# TestBed.net
KiCad netlist of a schematic drawn in EAGLE
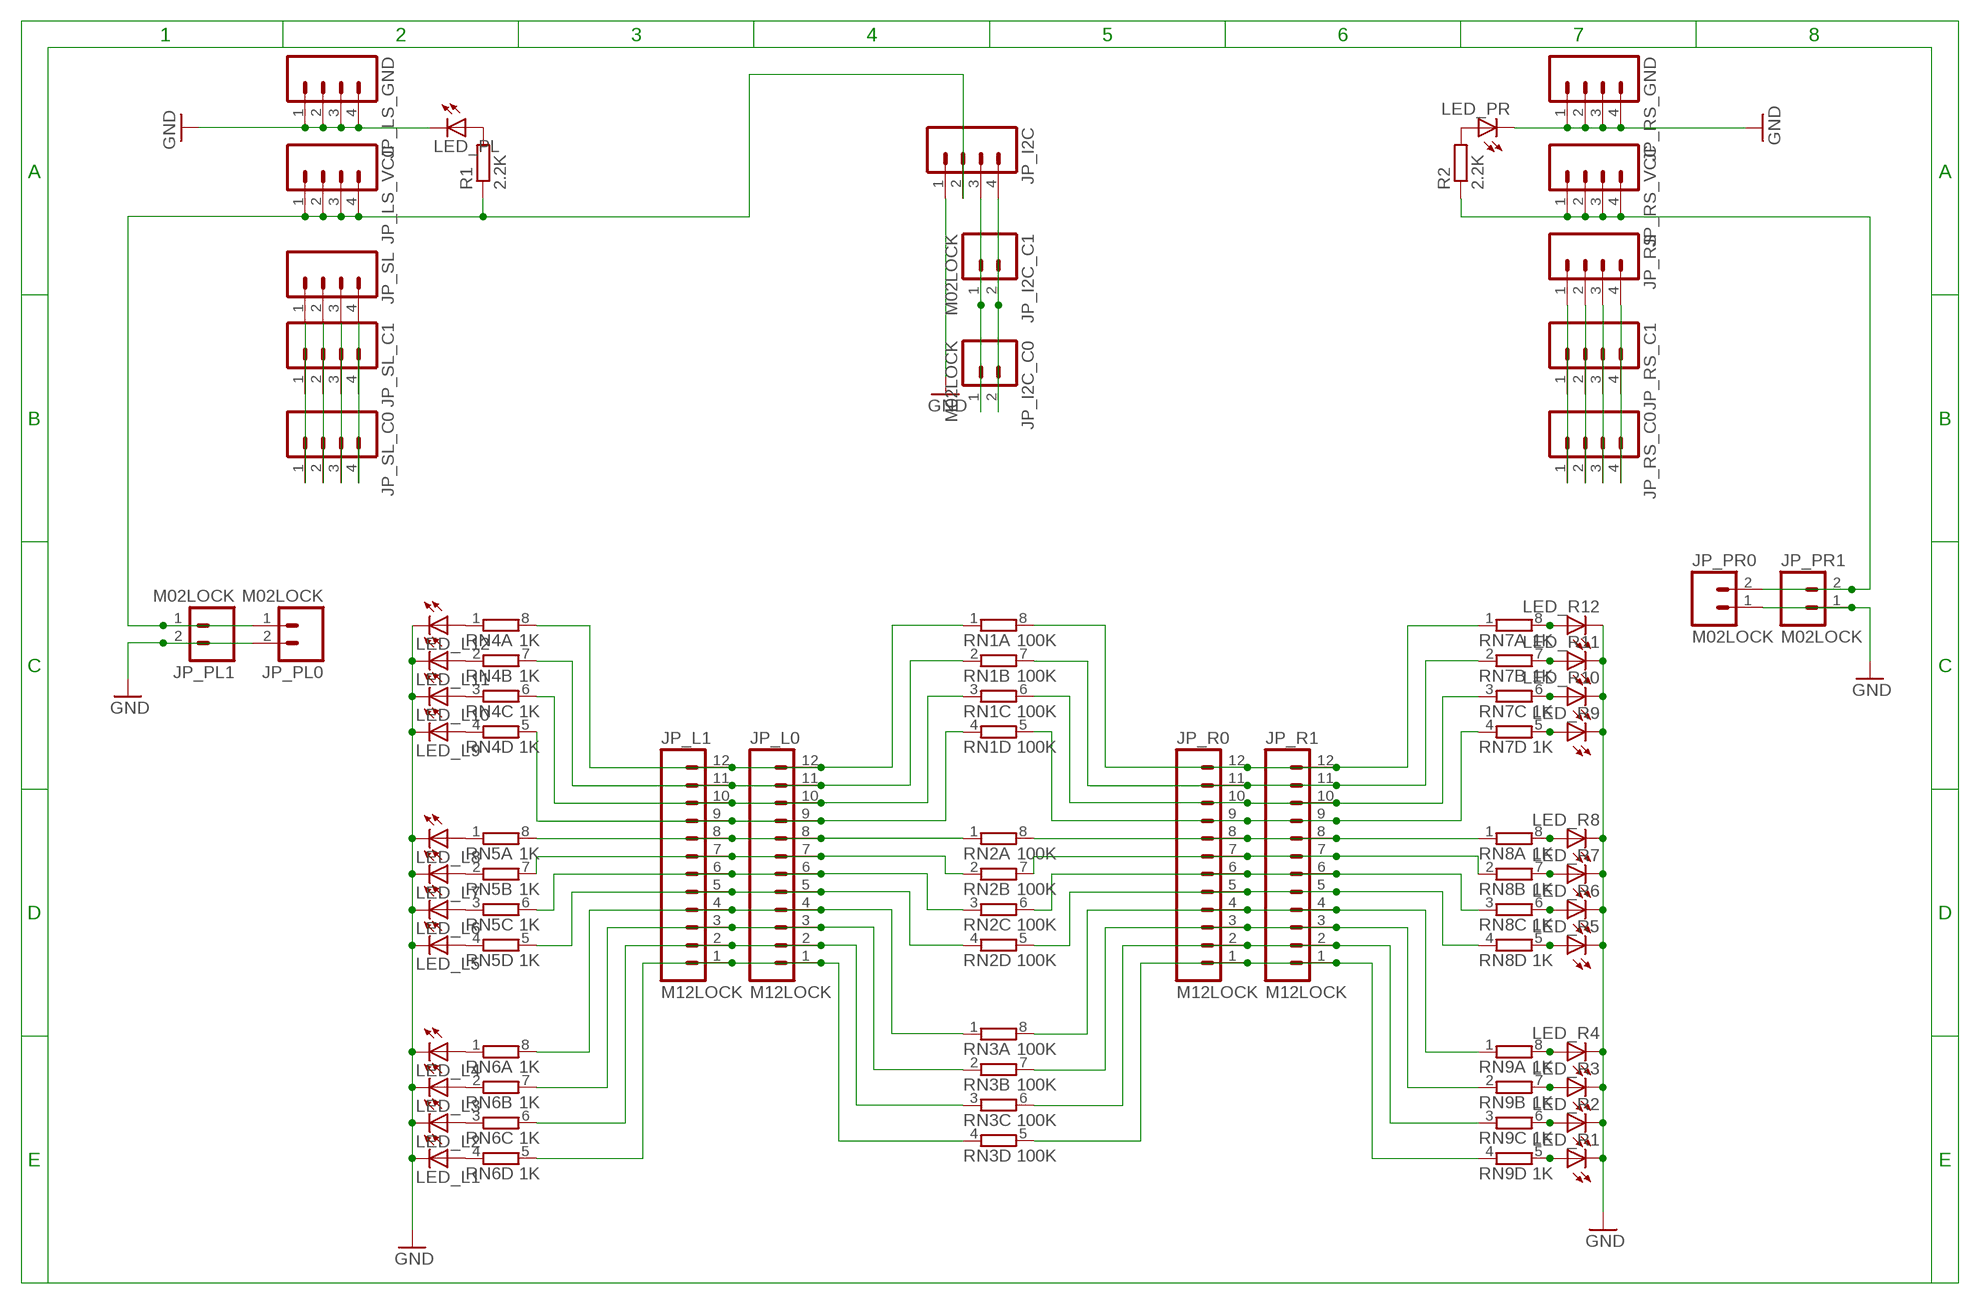
[diagram p0: schematic, sheet 1]

(export (version "E")
  (design (tool "Eeschema 10.0.6"))
  (components
    (comp (ref "JP_I2C")
      (value "M04LOCK")
      (footprint "eagle-import:1X04_LOCK")
      (libsource (lib "eagle-import") (part "M04LOCK"))
    )
    (comp (ref "JP_I2C_C0")
      (value "M02LOCK")
      (footprint "eagle-import:1X02_LOCK")
      (libsource (lib "eagle-import") (part "M02LOCK"))
    )
    (comp (ref "JP_I2C_C1")
      (value "M02LOCK")
      (footprint "eagle-import:1X02_LOCK")
      (libsource (lib "eagle-import") (part "M02LOCK"))
    )
    (comp (ref "JP_L0")
      (value "M12LOCK")
      (footprint "eagle-import:1X12_LOCK")
      (libsource (lib "eagle-import") (part "M12LOCK"))
    )
    (comp (ref "JP_L1")
      (value "M12LOCK")
      (footprint "eagle-import:1X12_LOCK")
      (libsource (lib "eagle-import") (part "M12LOCK"))
    )
    (comp (ref "JP_LS_GND")
      (value "M04LOCK")
      (footprint "eagle-import:1X04_LOCK")
      (libsource (lib "eagle-import") (part "M04LOCK"))
    )
    (comp (ref "JP_LS_VCC")
      (value "M04LOCK")
      (footprint "eagle-import:1X04_LOCK")
      (libsource (lib "eagle-import") (part "M04LOCK"))
    )
    (comp (ref "JP_PL0")
      (value "M02LOCK")
      (footprint "eagle-import:1X02_LOCK")
      (libsource (lib "eagle-import") (part "M02LOCK"))
    )
    (comp (ref "JP_PL1")
      (value "M02LOCK")
      (footprint "eagle-import:1X02_LOCK")
      (libsource (lib "eagle-import") (part "M02LOCK"))
    )
    (comp (ref "JP_PR0")
      (value "M02LOCK")
      (footprint "eagle-import:1X02_LOCK")
      (libsource (lib "eagle-import") (part "M02LOCK"))
    )
    (comp (ref "JP_PR1")
      (value "M02LOCK")
      (footprint "eagle-import:1X02_LOCK")
      (libsource (lib "eagle-import") (part "M02LOCK"))
    )
    (comp (ref "JP_R0")
      (value "M12LOCK")
      (footprint "eagle-import:1X12_LOCK")
      (libsource (lib "eagle-import") (part "M12LOCK"))
    )
    (comp (ref "JP_R1")
      (value "M12LOCK")
      (footprint "eagle-import:1X12_LOCK")
      (libsource (lib "eagle-import") (part "M12LOCK"))
    )
    (comp (ref "JP_RS")
      (value "M04LOCK")
      (footprint "eagle-import:1X04_LOCK")
      (libsource (lib "eagle-import") (part "M04LOCK"))
    )
    (comp (ref "JP_RS_C0")
      (value "M04LOCK")
      (footprint "eagle-import:1X04_LOCK")
      (libsource (lib "eagle-import") (part "M04LOCK"))
    )
    (comp (ref "JP_RS_C1")
      (value "M04LOCK")
      (footprint "eagle-import:1X04_LOCK")
      (libsource (lib "eagle-import") (part "M04LOCK"))
    )
    (comp (ref "JP_RS_GND")
      (value "M04LOCK")
      (footprint "eagle-import:1X04_LOCK")
      (libsource (lib "eagle-import") (part "M04LOCK"))
    )
    (comp (ref "JP_RS_VCC")
      (value "M04LOCK")
      (footprint "eagle-import:1X04_LOCK")
      (libsource (lib "eagle-import") (part "M04LOCK"))
    )
    (comp (ref "JP_SL")
      (value "M04LOCK")
      (footprint "eagle-import:1X04_LOCK")
      (libsource (lib "eagle-import") (part "M04LOCK"))
    )
    (comp (ref "JP_SL_C0")
      (value "M04LOCK")
      (footprint "eagle-import:1X04_LOCK")
      (libsource (lib "eagle-import") (part "M04LOCK"))
    )
    (comp (ref "JP_SL_C1")
      (value "M04LOCK")
      (footprint "eagle-import:1X04_LOCK")
      (libsource (lib "eagle-import") (part "M04LOCK"))
    )
    (comp (ref "LED_L1")
      (value "LEDCHIP-LED0805")
      (footprint "eagle-import:CHIP-LED0805")
      (libsource (lib "eagle-import") (part "LEDCHIP-LED0805"))
    )
    (comp (ref "LED_L2")
      (value "LEDCHIP-LED0805")
      (footprint "eagle-import:CHIP-LED0805")
      (libsource (lib "eagle-import") (part "LEDCHIP-LED0805"))
    )
    (comp (ref "LED_L3")
      (value "LEDCHIP-LED0805")
      (footprint "eagle-import:CHIP-LED0805")
      (libsource (lib "eagle-import") (part "LEDCHIP-LED0805"))
    )
    (comp (ref "LED_L4")
      (value "LEDCHIP-LED0805")
      (footprint "eagle-import:CHIP-LED0805")
      (libsource (lib "eagle-import") (part "LEDCHIP-LED0805"))
    )
    (comp (ref "LED_L5")
      (value "LEDCHIP-LED0805")
      (footprint "eagle-import:CHIP-LED0805")
      (libsource (lib "eagle-import") (part "LEDCHIP-LED0805"))
    )
    (comp (ref "LED_L6")
      (value "LEDCHIP-LED0805")
      (footprint "eagle-import:CHIP-LED0805")
      (libsource (lib "eagle-import") (part "LEDCHIP-LED0805"))
    )
    (comp (ref "LED_L7")
      (value "LEDCHIP-LED0805")
      (footprint "eagle-import:CHIP-LED0805")
      (libsource (lib "eagle-import") (part "LEDCHIP-LED0805"))
    )
    (comp (ref "LED_L8")
      (value "LEDCHIP-LED0805")
      (footprint "eagle-import:CHIP-LED0805")
      (libsource (lib "eagle-import") (part "LEDCHIP-LED0805"))
    )
    (comp (ref "LED_L9")
      (value "LEDCHIP-LED0805")
      (footprint "eagle-import:CHIP-LED0805")
      (libsource (lib "eagle-import") (part "LEDCHIP-LED0805"))
    )
    (comp (ref "LED_L10")
      (value "LEDCHIP-LED0805")
      (footprint "eagle-import:CHIP-LED0805")
      (libsource (lib "eagle-import") (part "LEDCHIP-LED0805"))
    )
    (comp (ref "LED_L11")
      (value "LEDCHIP-LED0805")
      (footprint "eagle-import:CHIP-LED0805")
      (libsource (lib "eagle-import") (part "LEDCHIP-LED0805"))
    )
    (comp (ref "LED_L12")
      (value "LEDCHIP-LED0805")
      (footprint "eagle-import:CHIP-LED0805")
      (libsource (lib "eagle-import") (part "LEDCHIP-LED0805"))
    )
    (comp (ref "LED_PL")
      (value "LEDCHIP-LED0805")
      (footprint "eagle-import:CHIP-LED0805")
      (libsource (lib "eagle-import") (part "LEDCHIP-LED0805"))
    )
    (comp (ref "LED_PR")
      (value "LEDCHIP-LED0805")
      (footprint "eagle-import:CHIP-LED0805")
      (libsource (lib "eagle-import") (part "LEDCHIP-LED0805"))
    )
    (comp (ref "LED_R1")
      (value "LEDCHIP-LED0805")
      (footprint "eagle-import:CHIP-LED0805")
      (libsource (lib "eagle-import") (part "LEDCHIP-LED0805"))
    )
    (comp (ref "LED_R2")
      (value "LEDCHIP-LED0805")
      (footprint "eagle-import:CHIP-LED0805")
      (libsource (lib "eagle-import") (part "LEDCHIP-LED0805"))
    )
    (comp (ref "LED_R3")
      (value "LEDCHIP-LED0805")
      (footprint "eagle-import:CHIP-LED0805")
      (libsource (lib "eagle-import") (part "LEDCHIP-LED0805"))
    )
    (comp (ref "LED_R4")
      (value "LEDCHIP-LED0805")
      (footprint "eagle-import:CHIP-LED0805")
      (libsource (lib "eagle-import") (part "LEDCHIP-LED0805"))
    )
    (comp (ref "LED_R5")
      (value "LEDCHIP-LED0805")
      (footprint "eagle-import:CHIP-LED0805")
      (libsource (lib "eagle-import") (part "LEDCHIP-LED0805"))
    )
    (comp (ref "LED_R6")
      (value "LEDCHIP-LED0805")
      (footprint "eagle-import:CHIP-LED0805")
      (libsource (lib "eagle-import") (part "LEDCHIP-LED0805"))
    )
    (comp (ref "LED_R7")
      (value "LEDCHIP-LED0805")
      (footprint "eagle-import:CHIP-LED0805")
      (libsource (lib "eagle-import") (part "LEDCHIP-LED0805"))
    )
    (comp (ref "LED_R8")
      (value "LEDCHIP-LED0805")
      (footprint "eagle-import:CHIP-LED0805")
      (libsource (lib "eagle-import") (part "LEDCHIP-LED0805"))
    )
    (comp (ref "LED_R9")
      (value "LEDCHIP-LED0805")
      (footprint "eagle-import:CHIP-LED0805")
      (libsource (lib "eagle-import") (part "LEDCHIP-LED0805"))
    )
    (comp (ref "LED_R10")
      (value "LEDCHIP-LED0805")
      (footprint "eagle-import:CHIP-LED0805")
      (libsource (lib "eagle-import") (part "LEDCHIP-LED0805"))
    )
    (comp (ref "LED_R11")
      (value "LEDCHIP-LED0805")
      (footprint "eagle-import:CHIP-LED0805")
      (libsource (lib "eagle-import") (part "LEDCHIP-LED0805"))
    )
    (comp (ref "LED_R12")
      (value "LEDCHIP-LED0805")
      (footprint "eagle-import:CHIP-LED0805")
      (libsource (lib "eagle-import") (part "LEDCHIP-LED0805"))
    )
    (comp (ref "R1")
      (value "2.2K")
      (footprint "eagle-import:M0805")
      (libsource (lib "eagle-import") (part "R-EU_M0805"))
    )
    (comp (ref "R2")
      (value "2.2K")
      (footprint "eagle-import:M0805")
      (libsource (lib "eagle-import") (part "R-EU_M0805"))
    )
    (comp (ref "RN1")
      (value "100K")
      (footprint "eagle-import:EXBS8V")
      (libsource (lib "eagle-import") (part "4R-NEXBS8V"))
    )
    (comp (ref "RN2")
      (value "100K")
      (footprint "eagle-import:EXBS8V")
      (libsource (lib "eagle-import") (part "4R-NEXBS8V"))
    )
    (comp (ref "RN3")
      (value "100K")
      (footprint "eagle-import:EXBS8V")
      (libsource (lib "eagle-import") (part "4R-NEXBS8V"))
    )
    (comp (ref "RN4")
      (value "1K")
      (footprint "eagle-import:EXBS8V")
      (libsource (lib "eagle-import") (part "4R-NEXBS8V"))
    )
    (comp (ref "RN5")
      (value "1K")
      (footprint "eagle-import:EXBS8V")
      (libsource (lib "eagle-import") (part "4R-NEXBS8V"))
    )
    (comp (ref "RN6")
      (value "1K")
      (footprint "eagle-import:EXBS8V")
      (libsource (lib "eagle-import") (part "4R-NEXBS8V"))
    )
    (comp (ref "RN7")
      (value "1K")
      (footprint "eagle-import:EXBS8V")
      (libsource (lib "eagle-import") (part "4R-NEXBS8V"))
    )
    (comp (ref "RN8")
      (value "1K")
      (footprint "eagle-import:EXBS8V")
      (libsource (lib "eagle-import") (part "4R-NEXBS8V"))
    )
    (comp (ref "RN9")
      (value "1K")
      (footprint "eagle-import:EXBS8V")
      (libsource (lib "eagle-import") (part "4R-NEXBS8V"))
    )
  )
  (nets
    (net (code "1") (name "GND") (class "Default")
      (node (ref "JP_I2C") (pin "1") (pinfunction "1_1") (pintype "passive"))
      (node (ref "JP_LS_GND") (pin "1") (pinfunction "1_1") (pintype "passive"))
      (node (ref "JP_LS_GND") (pin "2") (pinfunction "2_2") (pintype "passive"))
      (node (ref "JP_LS_GND") (pin "3") (pinfunction "3_3") (pintype "passive"))
      (node (ref "JP_LS_GND") (pin "4") (pinfunction "4_4") (pintype "passive"))
      (node (ref "JP_PL0") (pin "2") (pinfunction "2_2") (pintype "passive"))
      (node (ref "JP_PL1") (pin "2") (pinfunction "2_2") (pintype "passive"))
      (node (ref "JP_PR0") (pin "1") (pinfunction "1_1") (pintype "passive"))
      (node (ref "JP_PR1") (pin "1") (pinfunction "1_1") (pintype "passive"))
      (node (ref "JP_RS_GND") (pin "1") (pinfunction "1_1") (pintype "passive"))
      (node (ref "JP_RS_GND") (pin "2") (pinfunction "2_2") (pintype "passive"))
      (node (ref "JP_RS_GND") (pin "3") (pinfunction "3_3") (pintype "passive"))
      (node (ref "JP_RS_GND") (pin "4") (pinfunction "4_4") (pintype "passive"))
      (node (ref "LED_L1") (pin "C") (pinfunction "C_C") (pintype "passive"))
      (node (ref "LED_L10") (pin "C") (pinfunction "C_C") (pintype "passive"))
      (node (ref "LED_L11") (pin "C") (pinfunction "C_C") (pintype "passive"))
      (node (ref "LED_L12") (pin "C") (pinfunction "C_C") (pintype "passive"))
      (node (ref "LED_L2") (pin "C") (pinfunction "C_C") (pintype "passive"))
      (node (ref "LED_L3") (pin "C") (pinfunction "C_C") (pintype "passive"))
      (node (ref "LED_L4") (pin "C") (pinfunction "C_C") (pintype "passive"))
      (node (ref "LED_L5") (pin "C") (pinfunction "C_C") (pintype "passive"))
      (node (ref "LED_L6") (pin "C") (pinfunction "C_C") (pintype "passive"))
      (node (ref "LED_L7") (pin "C") (pinfunction "C_C") (pintype "passive"))
      (node (ref "LED_L8") (pin "C") (pinfunction "C_C") (pintype "passive"))
      (node (ref "LED_L9") (pin "C") (pinfunction "C_C") (pintype "passive"))
      (node (ref "LED_PL") (pin "C") (pinfunction "C_C") (pintype "passive"))
      (node (ref "LED_PR") (pin "C") (pinfunction "C_C") (pintype "passive"))
      (node (ref "LED_R1") (pin "C") (pinfunction "C_C") (pintype "passive"))
      (node (ref "LED_R10") (pin "C") (pinfunction "C_C") (pintype "passive"))
      (node (ref "LED_R11") (pin "C") (pinfunction "C_C") (pintype "passive"))
      (node (ref "LED_R12") (pin "C") (pinfunction "C_C") (pintype "passive"))
      (node (ref "LED_R2") (pin "C") (pinfunction "C_C") (pintype "passive"))
      (node (ref "LED_R3") (pin "C") (pinfunction "C_C") (pintype "passive"))
      (node (ref "LED_R4") (pin "C") (pinfunction "C_C") (pintype "passive"))
      (node (ref "LED_R5") (pin "C") (pinfunction "C_C") (pintype "passive"))
      (node (ref "LED_R6") (pin "C") (pinfunction "C_C") (pintype "passive"))
      (node (ref "LED_R7") (pin "C") (pinfunction "C_C") (pintype "passive"))
      (node (ref "LED_R8") (pin "C") (pinfunction "C_C") (pintype "passive"))
      (node (ref "LED_R9") (pin "C") (pinfunction "C_C") (pintype "passive"))
    )
    (net (code "2") (name "Net-(JP_I2C-Pad2)") (class "Default")
      (node (ref "JP_I2C") (pin "2") (pinfunction "2_2") (pintype "passive"))
      (node (ref "JP_LS_VCC") (pin "1") (pinfunction "1_1") (pintype "passive"))
      (node (ref "JP_LS_VCC") (pin "2") (pinfunction "2_2") (pintype "passive"))
      (node (ref "JP_LS_VCC") (pin "3") (pinfunction "3_3") (pintype "passive"))
      (node (ref "JP_LS_VCC") (pin "4") (pinfunction "4_4") (pintype "passive"))
      (node (ref "JP_PL0") (pin "1") (pinfunction "1_1") (pintype "passive"))
      (node (ref "JP_PL1") (pin "1") (pinfunction "1_1") (pintype "passive"))
      (node (ref "R1") (pin "1") (pinfunction "1_1") (pintype "passive"))
    )
    (net (code "3") (name "Net-(JP_I2C-Pad3)") (class "Default")
      (node (ref "JP_I2C") (pin "3") (pinfunction "3_3") (pintype "passive"))
      (node (ref "JP_I2C_C0") (pin "1") (pinfunction "1_1") (pintype "passive"))
      (node (ref "JP_I2C_C1") (pin "1") (pinfunction "1_1") (pintype "passive"))
    )
    (net (code "4") (name "Net-(JP_I2C-Pad4)") (class "Default")
      (node (ref "JP_I2C") (pin "4") (pinfunction "4_4") (pintype "passive"))
      (node (ref "JP_I2C_C0") (pin "2") (pinfunction "2_2") (pintype "passive"))
      (node (ref "JP_I2C_C1") (pin "2") (pinfunction "2_2") (pintype "passive"))
    )
    (net (code "5") (name "Net-(JP_PR0-Pad2)") (class "Default")
      (node (ref "JP_PR0") (pin "2") (pinfunction "2_2") (pintype "passive"))
      (node (ref "JP_PR1") (pin "2") (pinfunction "2_2") (pintype "passive"))
      (node (ref "JP_RS_VCC") (pin "1") (pinfunction "1_1") (pintype "passive"))
      (node (ref "JP_RS_VCC") (pin "2") (pinfunction "2_2") (pintype "passive"))
      (node (ref "JP_RS_VCC") (pin "3") (pinfunction "3_3") (pintype "passive"))
      (node (ref "JP_RS_VCC") (pin "4") (pinfunction "4_4") (pintype "passive"))
      (node (ref "R2") (pin "1") (pinfunction "1_1") (pintype "passive"))
    )
    (net (code "6") (name "Net-(JP_RS-Pad1)") (class "Default")
      (node (ref "JP_RS") (pin "1") (pinfunction "1_1") (pintype "passive"))
      (node (ref "JP_RS_C0") (pin "1") (pinfunction "1_1") (pintype "passive"))
      (node (ref "JP_RS_C1") (pin "1") (pinfunction "1_1") (pintype "passive"))
    )
    (net (code "7") (name "Net-(JP_RS-Pad2)") (class "Default")
      (node (ref "JP_RS") (pin "2") (pinfunction "2_2") (pintype "passive"))
      (node (ref "JP_RS_C0") (pin "2") (pinfunction "2_2") (pintype "passive"))
      (node (ref "JP_RS_C1") (pin "2") (pinfunction "2_2") (pintype "passive"))
    )
    (net (code "8") (name "Net-(JP_RS-Pad3)") (class "Default")
      (node (ref "JP_RS") (pin "3") (pinfunction "3_3") (pintype "passive"))
      (node (ref "JP_RS_C0") (pin "3") (pinfunction "3_3") (pintype "passive"))
      (node (ref "JP_RS_C1") (pin "3") (pinfunction "3_3") (pintype "passive"))
    )
    (net (code "9") (name "Net-(JP_RS-Pad4)") (class "Default")
      (node (ref "JP_RS") (pin "4") (pinfunction "4_4") (pintype "passive"))
      (node (ref "JP_RS_C0") (pin "4") (pinfunction "4_4") (pintype "passive"))
      (node (ref "JP_RS_C1") (pin "4") (pinfunction "4_4") (pintype "passive"))
    )
    (net (code "10") (name "Net-(JP_SL-Pad1)") (class "Default")
      (node (ref "JP_SL") (pin "1") (pinfunction "1_1") (pintype "passive"))
      (node (ref "JP_SL_C0") (pin "1") (pinfunction "1_1") (pintype "passive"))
      (node (ref "JP_SL_C1") (pin "1") (pinfunction "1_1") (pintype "passive"))
    )
    (net (code "11") (name "Net-(JP_SL-Pad2)") (class "Default")
      (node (ref "JP_SL") (pin "2") (pinfunction "2_2") (pintype "passive"))
      (node (ref "JP_SL_C0") (pin "2") (pinfunction "2_2") (pintype "passive"))
      (node (ref "JP_SL_C1") (pin "2") (pinfunction "2_2") (pintype "passive"))
    )
    (net (code "12") (name "Net-(JP_SL-Pad3)") (class "Default")
      (node (ref "JP_SL") (pin "3") (pinfunction "3_3") (pintype "passive"))
      (node (ref "JP_SL_C0") (pin "3") (pinfunction "3_3") (pintype "passive"))
      (node (ref "JP_SL_C1") (pin "3") (pinfunction "3_3") (pintype "passive"))
    )
    (net (code "13") (name "Net-(JP_SL-Pad4)") (class "Default")
      (node (ref "JP_SL") (pin "4") (pinfunction "4_4") (pintype "passive"))
      (node (ref "JP_SL_C0") (pin "4") (pinfunction "4_4") (pintype "passive"))
      (node (ref "JP_SL_C1") (pin "4") (pinfunction "4_4") (pintype "passive"))
    )
    (net (code "14") (name "Net-(LED_L4-PadA)") (class "Default")
      (node (ref "LED_L4") (pin "A") (pinfunction "A_A") (pintype "passive"))
      (node (ref "RN6") (pin "1") (pinfunction "1_1") (pintype "passive"))
    )
    (net (code "15") (name "Net-(LED_L8-PadA)") (class "Default")
      (node (ref "LED_L8") (pin "A") (pinfunction "A_A") (pintype "passive"))
      (node (ref "RN5") (pin "1") (pinfunction "1_1") (pintype "passive"))
    )
    (net (code "16") (name "Net-(LED_L12-PadA)") (class "Default")
      (node (ref "LED_L12") (pin "A") (pinfunction "A_A") (pintype "passive"))
      (node (ref "RN4") (pin "1") (pinfunction "1_1") (pintype "passive"))
    )
    (net (code "17") (name "Net-(LED_PL-PadA)") (class "Default")
      (node (ref "LED_PL") (pin "A") (pinfunction "A_A") (pintype "passive"))
      (node (ref "R1") (pin "2") (pinfunction "2_2") (pintype "passive"))
    )
    (net (code "18") (name "Net-(LED_PR-PadA)") (class "Default")
      (node (ref "LED_PR") (pin "A") (pinfunction "A_A") (pintype "passive"))
      (node (ref "R2") (pin "2") (pinfunction "2_2") (pintype "passive"))
    )
    (net (code "19") (name "Net-(RN1A-2)") (class "Default")
      (node (ref "JP_R0") (pin "12") (pinfunction "12_12") (pintype "passive"))
      (node (ref "JP_R1") (pin "12") (pinfunction "12_12") (pintype "passive"))
      (node (ref "RN1") (pin "8") (pinfunction "2_8") (pintype "passive"))
      (node (ref "RN7") (pin "1") (pinfunction "1_1") (pintype "passive"))
    )
    (net (code "20") (name "Net-(RN1B-1)") (class "Default")
      (node (ref "JP_L0") (pin "11") (pinfunction "11_11") (pintype "passive"))
      (node (ref "JP_L1") (pin "11") (pinfunction "11_11") (pintype "passive"))
      (node (ref "RN1") (pin "2") (pinfunction "1_2") (pintype "passive"))
      (node (ref "RN4") (pin "7") (pinfunction "2_7") (pintype "passive"))
    )
    (net (code "21") (name "Net-(RN1B-2)") (class "Default")
      (node (ref "JP_R0") (pin "11") (pinfunction "11_11") (pintype "passive"))
      (node (ref "JP_R1") (pin "11") (pinfunction "11_11") (pintype "passive"))
      (node (ref "RN1") (pin "7") (pinfunction "2_7") (pintype "passive"))
      (node (ref "RN7") (pin "2") (pinfunction "1_2") (pintype "passive"))
    )
    (net (code "22") (name "Net-(RN1C-1)") (class "Default")
      (node (ref "JP_L0") (pin "10") (pinfunction "10_10") (pintype "passive"))
      (node (ref "JP_L1") (pin "10") (pinfunction "10_10") (pintype "passive"))
      (node (ref "RN1") (pin "3") (pinfunction "1_3") (pintype "passive"))
      (node (ref "RN4") (pin "6") (pinfunction "2_6") (pintype "passive"))
    )
    (net (code "23") (name "Net-(RN1C-2)") (class "Default")
      (node (ref "JP_R0") (pin "10") (pinfunction "10_10") (pintype "passive"))
      (node (ref "JP_R1") (pin "10") (pinfunction "10_10") (pintype "passive"))
      (node (ref "RN1") (pin "6") (pinfunction "2_6") (pintype "passive"))
      (node (ref "RN7") (pin "3") (pinfunction "1_3") (pintype "passive"))
    )
    (net (code "24") (name "Net-(RN1D-1)") (class "Default")
      (node (ref "JP_L0") (pin "9") (pinfunction "9_9") (pintype "passive"))
      (node (ref "JP_L1") (pin "9") (pinfunction "9_9") (pintype "passive"))
      (node (ref "RN1") (pin "4") (pinfunction "1_4") (pintype "passive"))
      (node (ref "RN4") (pin "5") (pinfunction "2_5") (pintype "passive"))
    )
    (net (code "25") (name "Net-(RN1D-2)") (class "Default")
      (node (ref "JP_R0") (pin "9") (pinfunction "9_9") (pintype "passive"))
      (node (ref "JP_R1") (pin "9") (pinfunction "9_9") (pintype "passive"))
      (node (ref "RN1") (pin "5") (pinfunction "2_5") (pintype "passive"))
      (node (ref "RN7") (pin "4") (pinfunction "1_4") (pintype "passive"))
    )
    (net (code "26") (name "Net-(RN2A-2)") (class "Default")
      (node (ref "JP_R0") (pin "8") (pinfunction "8_8") (pintype "passive"))
      (node (ref "JP_R1") (pin "8") (pinfunction "8_8") (pintype "passive"))
      (node (ref "RN2") (pin "8") (pinfunction "2_8") (pintype "passive"))
      (node (ref "RN8") (pin "1") (pinfunction "1_1") (pintype "passive"))
    )
    (net (code "27") (name "Net-(RN2B-1)") (class "Default")
      (node (ref "JP_L0") (pin "7") (pinfunction "7_7") (pintype "passive"))
      (node (ref "JP_L1") (pin "7") (pinfunction "7_7") (pintype "passive"))
      (node (ref "RN2") (pin "2") (pinfunction "1_2") (pintype "passive"))
      (node (ref "RN5") (pin "7") (pinfunction "2_7") (pintype "passive"))
    )
    (net (code "28") (name "Net-(RN2B-2)") (class "Default")
      (node (ref "JP_R0") (pin "7") (pinfunction "7_7") (pintype "passive"))
      (node (ref "JP_R1") (pin "7") (pinfunction "7_7") (pintype "passive"))
      (node (ref "RN2") (pin "7") (pinfunction "2_7") (pintype "passive"))
      (node (ref "RN8") (pin "2") (pinfunction "1_2") (pintype "passive"))
    )
    (net (code "29") (name "Net-(RN2C-1)") (class "Default")
      (node (ref "JP_L0") (pin "6") (pinfunction "6_6") (pintype "passive"))
      (node (ref "JP_L1") (pin "6") (pinfunction "6_6") (pintype "passive"))
      (node (ref "RN2") (pin "3") (pinfunction "1_3") (pintype "passive"))
      (node (ref "RN5") (pin "6") (pinfunction "2_6") (pintype "passive"))
    )
    (net (code "30") (name "Net-(RN2C-2)") (class "Default")
      (node (ref "JP_R0") (pin "6") (pinfunction "6_6") (pintype "passive"))
      (node (ref "JP_R1") (pin "6") (pinfunction "6_6") (pintype "passive"))
      (node (ref "RN2") (pin "6") (pinfunction "2_6") (pintype "passive"))
      (node (ref "RN8") (pin "3") (pinfunction "1_3") (pintype "passive"))
    )
    (net (code "31") (name "Net-(RN2D-1)") (class "Default")
      (node (ref "JP_L0") (pin "5") (pinfunction "5_5") (pintype "passive"))
      (node (ref "JP_L1") (pin "5") (pinfunction "5_5") (pintype "passive"))
      (node (ref "RN2") (pin "4") (pinfunction "1_4") (pintype "passive"))
      (node (ref "RN5") (pin "5") (pinfunction "2_5") (pintype "passive"))
    )
    (net (code "32") (name "Net-(RN2D-2)") (class "Default")
      (node (ref "JP_R0") (pin "5") (pinfunction "5_5") (pintype "passive"))
      (node (ref "JP_R1") (pin "5") (pinfunction "5_5") (pintype "passive"))
      (node (ref "RN2") (pin "5") (pinfunction "2_5") (pintype "passive"))
      (node (ref "RN8") (pin "4") (pinfunction "1_4") (pintype "passive"))
    )
    (net (code "33") (name "Net-(RN3A-2)") (class "Default")
      (node (ref "JP_R0") (pin "4") (pinfunction "4_4") (pintype "passive"))
      (node (ref "JP_R1") (pin "4") (pinfunction "4_4") (pintype "passive"))
      (node (ref "RN3") (pin "8") (pinfunction "2_8") (pintype "passive"))
      (node (ref "RN9") (pin "1") (pinfunction "1_1") (pintype "passive"))
    )
    (net (code "34") (name "Net-(RN3B-1)") (class "Default")
      (node (ref "JP_L0") (pin "3") (pinfunction "3_3") (pintype "passive"))
      (node (ref "JP_L1") (pin "3") (pinfunction "3_3") (pintype "passive"))
      (node (ref "RN3") (pin "2") (pinfunction "1_2") (pintype "passive"))
      (node (ref "RN6") (pin "7") (pinfunction "2_7") (pintype "passive"))
    )
    (net (code "35") (name "Net-(RN3B-2)") (class "Default")
      (node (ref "JP_R0") (pin "3") (pinfunction "3_3") (pintype "passive"))
      (node (ref "JP_R1") (pin "3") (pinfunction "3_3") (pintype "passive"))
      (node (ref "RN3") (pin "7") (pinfunction "2_7") (pintype "passive"))
      (node (ref "RN9") (pin "2") (pinfunction "1_2") (pintype "passive"))
    )
    (net (code "36") (name "Net-(RN3C-1)") (class "Default")
      (node (ref "JP_L0") (pin "2") (pinfunction "2_2") (pintype "passive"))
      (node (ref "JP_L1") (pin "2") (pinfunction "2_2") (pintype "passive"))
      (node (ref "RN3") (pin "3") (pinfunction "1_3") (pintype "passive"))
      (node (ref "RN6") (pin "6") (pinfunction "2_6") (pintype "passive"))
    )
    (net (code "37") (name "Net-(RN3C-2)") (class "Default")
      (node (ref "JP_R0") (pin "2") (pinfunction "2_2") (pintype "passive"))
      (node (ref "JP_R1") (pin "2") (pinfunction "2_2") (pintype "passive"))
      (node (ref "RN3") (pin "6") (pinfunction "2_6") (pintype "passive"))
      (node (ref "RN9") (pin "3") (pinfunction "1_3") (pintype "passive"))
    )
    (net (code "38") (name "Net-(RN3D-1)") (class "Default")
      (node (ref "JP_L0") (pin "1") (pinfunction "1_1") (pintype "passive"))
      (node (ref "JP_L1") (pin "1") (pinfunction "1_1") (pintype "passive"))
      (node (ref "RN3") (pin "4") (pinfunction "1_4") (pintype "passive"))
      (node (ref "RN6") (pin "5") (pinfunction "2_5") (pintype "passive"))
    )
    (net (code "39") (name "Net-(RN3D-2)") (class "Default")
      (node (ref "JP_R0") (pin "1") (pinfunction "1_1") (pintype "passive"))
      (node (ref "JP_R1") (pin "1") (pinfunction "1_1") (pintype "passive"))
      (node (ref "RN3") (pin "5") (pinfunction "2_5") (pintype "passive"))
      (node (ref "RN9") (pin "4") (pinfunction "1_4") (pintype "passive"))
    )
    (net (code "40") (name "Net-(RN4A-2)") (class "Default")
      (node (ref "JP_L0") (pin "12") (pinfunction "12_12") (pintype "passive"))
      (node (ref "JP_L1") (pin "12") (pinfunction "12_12") (pintype "passive"))
      (node (ref "RN1") (pin "1") (pinfunction "1_1") (pintype "passive"))
      (node (ref "RN4") (pin "8") (pinfunction "2_8") (pintype "passive"))
    )
    (net (code "41") (name "Net-(RN4B-1)") (class "Default")
      (node (ref "LED_L11") (pin "A") (pinfunction "A_A") (pintype "passive"))
      (node (ref "RN4") (pin "2") (pinfunction "1_2") (pintype "passive"))
    )
    (net (code "42") (name "Net-(RN4C-1)") (class "Default")
      (node (ref "LED_L10") (pin "A") (pinfunction "A_A") (pintype "passive"))
      (node (ref "RN4") (pin "3") (pinfunction "1_3") (pintype "passive"))
    )
    (net (code "43") (name "Net-(RN4D-1)") (class "Default")
      (node (ref "LED_L9") (pin "A") (pinfunction "A_A") (pintype "passive"))
      (node (ref "RN4") (pin "4") (pinfunction "1_4") (pintype "passive"))
    )
    (net (code "44") (name "Net-(RN5A-2)") (class "Default")
      (node (ref "JP_L0") (pin "8") (pinfunction "8_8") (pintype "passive"))
      (node (ref "JP_L1") (pin "8") (pinfunction "8_8") (pintype "passive"))
      (node (ref "RN2") (pin "1") (pinfunction "1_1") (pintype "passive"))
      (node (ref "RN5") (pin "8") (pinfunction "2_8") (pintype "passive"))
    )
    (net (code "45") (name "Net-(RN5B-1)") (class "Default")
      (node (ref "LED_L7") (pin "A") (pinfunction "A_A") (pintype "passive"))
      (node (ref "RN5") (pin "2") (pinfunction "1_2") (pintype "passive"))
    )
    (net (code "46") (name "Net-(RN5C-1)") (class "Default")
      (node (ref "LED_L6") (pin "A") (pinfunction "A_A") (pintype "passive"))
      (node (ref "RN5") (pin "3") (pinfunction "1_3") (pintype "passive"))
    )
    (net (code "47") (name "Net-(RN5D-1)") (class "Default")
      (node (ref "LED_L5") (pin "A") (pinfunction "A_A") (pintype "passive"))
      (node (ref "RN5") (pin "4") (pinfunction "1_4") (pintype "passive"))
    )
    (net (code "48") (name "Net-(RN6A-2)") (class "Default")
      (node (ref "JP_L0") (pin "4") (pinfunction "4_4") (pintype "passive"))
      (node (ref "JP_L1") (pin "4") (pinfunction "4_4") (pintype "passive"))
      (node (ref "RN3") (pin "1") (pinfunction "1_1") (pintype "passive"))
      (node (ref "RN6") (pin "8") (pinfunction "2_8") (pintype "passive"))
    )
    (net (code "49") (name "Net-(RN6B-1)") (class "Default")
      (node (ref "LED_L3") (pin "A") (pinfunction "A_A") (pintype "passive"))
      (node (ref "RN6") (pin "2") (pinfunction "1_2") (pintype "passive"))
    )
    (net (code "50") (name "Net-(RN6C-1)") (class "Default")
      (node (ref "LED_L2") (pin "A") (pinfunction "A_A") (pintype "passive"))
      (node (ref "RN6") (pin "3") (pinfunction "1_3") (pintype "passive"))
    )
    (net (code "51") (name "Net-(RN6D-1)") (class "Default")
      (node (ref "LED_L1") (pin "A") (pinfunction "A_A") (pintype "passive"))
      (node (ref "RN6") (pin "4") (pinfunction "1_4") (pintype "passive"))
    )
    (net (code "52") (name "Net-(RN7A-2)") (class "Default")
      (node (ref "LED_R12") (pin "A") (pinfunction "A_A") (pintype "passive"))
      (node (ref "RN7") (pin "8") (pinfunction "2_8") (pintype "passive"))
    )
    (net (code "53") (name "Net-(RN7B-2)") (class "Default")
      (node (ref "LED_R11") (pin "A") (pinfunction "A_A") (pintype "passive"))
      (node (ref "RN7") (pin "7") (pinfunction "2_7") (pintype "passive"))
    )
    (net (code "54") (name "Net-(RN7C-2)") (class "Default")
      (node (ref "LED_R10") (pin "A") (pinfunction "A_A") (pintype "passive"))
      (node (ref "RN7") (pin "6") (pinfunction "2_6") (pintype "passive"))
    )
    (net (code "55") (name "Net-(RN7D-2)") (class "Default")
      (node (ref "LED_R9") (pin "A") (pinfunction "A_A") (pintype "passive"))
      (node (ref "RN7") (pin "5") (pinfunction "2_5") (pintype "passive"))
    )
    (net (code "56") (name "Net-(RN8A-2)") (class "Default")
      (node (ref "LED_R8") (pin "A") (pinfunction "A_A") (pintype "passive"))
      (node (ref "RN8") (pin "8") (pinfunction "2_8") (pintype "passive"))
    )
    (net (code "57") (name "Net-(RN8B-2)") (class "Default")
      (node (ref "LED_R7") (pin "A") (pinfunction "A_A") (pintype "passive"))
      (node (ref "RN8") (pin "7") (pinfunction "2_7") (pintype "passive"))
    )
    (net (code "58") (name "Net-(RN8C-2)") (class "Default")
      (node (ref "LED_R6") (pin "A") (pinfunction "A_A") (pintype "passive"))
      (node (ref "RN8") (pin "6") (pinfunction "2_6") (pintype "passive"))
    )
    (net (code "59") (name "Net-(RN8D-2)") (class "Default")
      (node (ref "LED_R5") (pin "A") (pinfunction "A_A") (pintype "passive"))
      (node (ref "RN8") (pin "5") (pinfunction "2_5") (pintype "passive"))
    )
    (net (code "60") (name "Net-(RN9A-2)") (class "Default")
      (node (ref "LED_R4") (pin "A") (pinfunction "A_A") (pintype "passive"))
      (node (ref "RN9") (pin "8") (pinfunction "2_8") (pintype "passive"))
    )
    (net (code "61") (name "Net-(RN9B-2)") (class "Default")
      (node (ref "LED_R3") (pin "A") (pinfunction "A_A") (pintype "passive"))
      (node (ref "RN9") (pin "7") (pinfunction "2_7") (pintype "passive"))
    )
    (net (code "62") (name "Net-(RN9C-2)") (class "Default")
      (node (ref "LED_R2") (pin "A") (pinfunction "A_A") (pintype "passive"))
      (node (ref "RN9") (pin "6") (pinfunction "2_6") (pintype "passive"))
    )
    (net (code "63") (name "Net-(RN9D-2)") (class "Default")
      (node (ref "LED_R1") (pin "A") (pinfunction "A_A") (pintype "passive"))
      (node (ref "RN9") (pin "5") (pinfunction "2_5") (pintype "passive"))
    )
  )
)
